# Final_Main.net
KiCad netlist of a schematic drawn in EasyEDA Pro
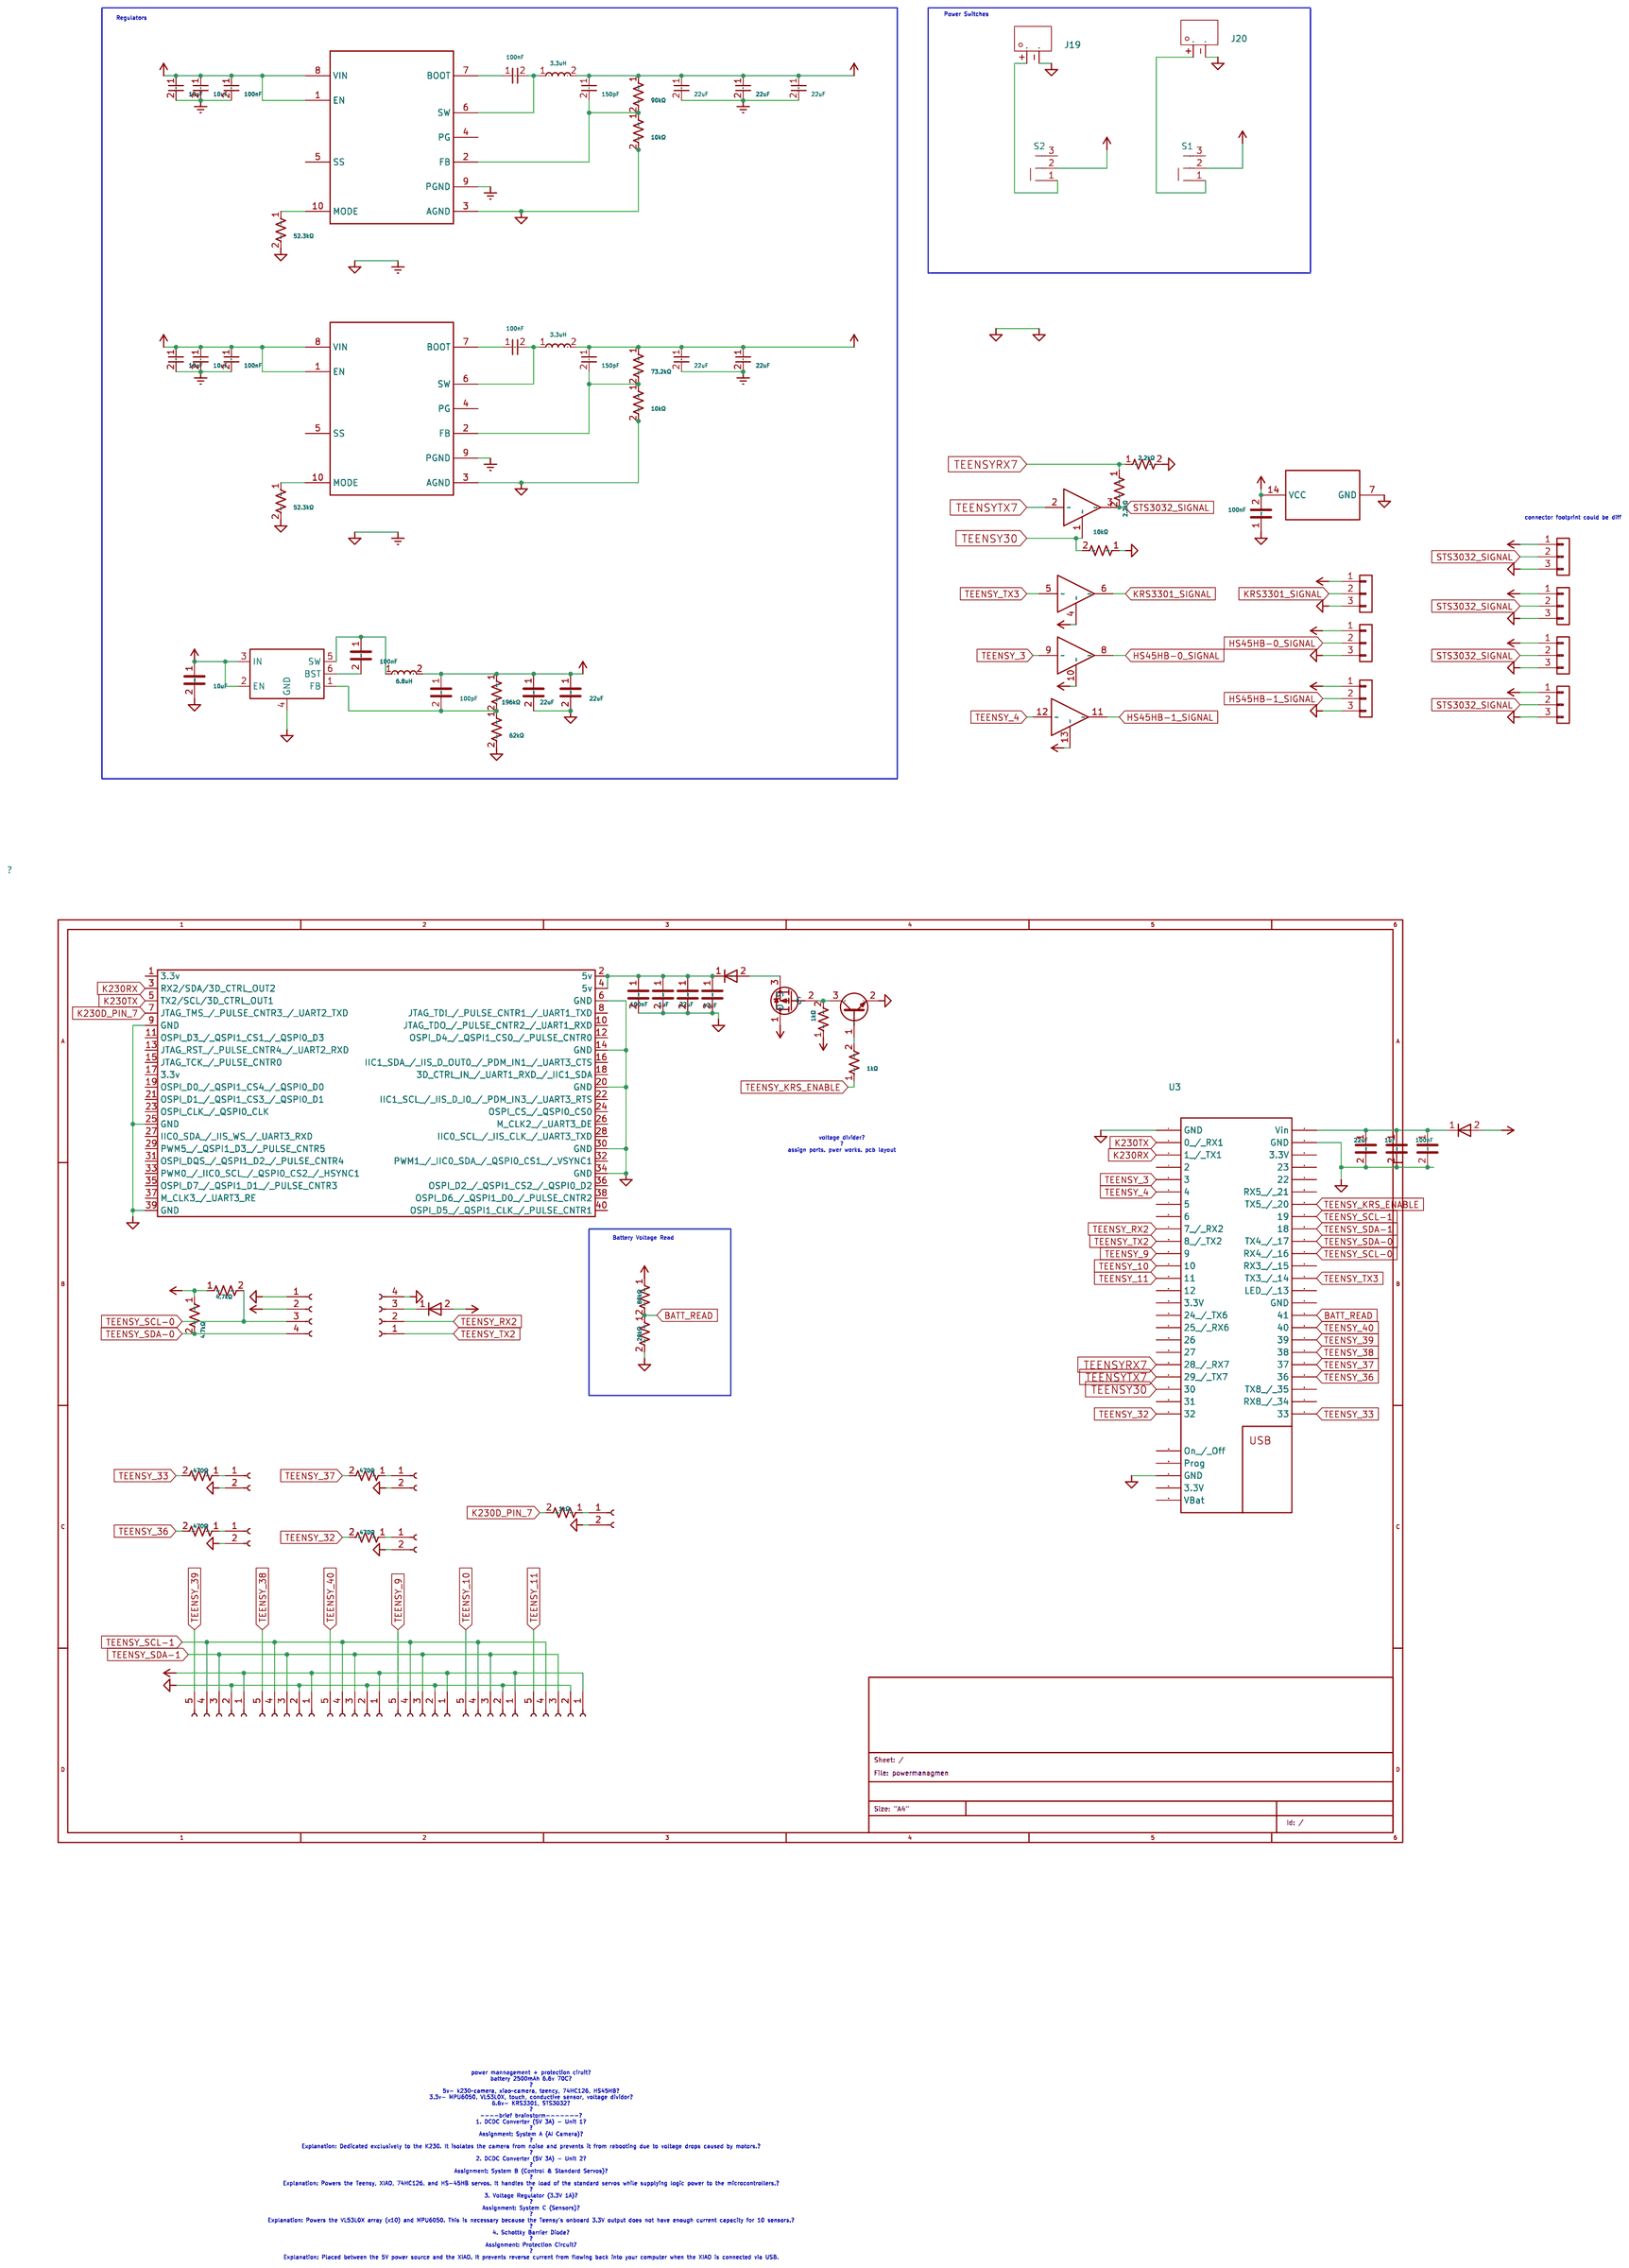
[diagram p0: schematic sheet]

(export (version "E")
  (design (tool "Eeschema 10.0.6"))
  (components
    (comp (ref "C1")
      (value "100nF")
      (description "Capacitance:100nF Tolerance:±10% Tolerance:±10% Voltage Rating:50V Temperature Coefficient:X7R")
      (fields
        (field (name "Manufacturer Part") "TCC0603X7R104K500CT")
        (field (name "Manufacturer") "CCTC(三环)")
      )
      (libsource (lib "easyedapro") (part "Device_C"))
    )
    (comp (ref "C2")
      (value "22uF")
      (description "Capacitance:22uF Tolerance:±20% Tolerance:±20% Voltage Rating:10V Temperature Coefficient:X5R")
      (fields
        (field (name "Manufacturer Part") "CL10A226MP8NUNE")
        (field (name "Manufacturer") "SAMSUNG(三星)")
      )
      (libsource (lib "easyedapro") (part "Device_C"))
    )
    (comp (ref "C3")
      (value "1uF")
      (description "Capacitance:1uF Tolerance:±10% Tolerance:±10% Voltage Rating:50V Temperature Coefficient:X5R")
      (fields
        (field (name "Manufacturer Part") "CL10A105KB8NNNC")
        (field (name "Manufacturer") "SAMSUNG(三星)")
      )
      (libsource (lib "easyedapro") (part "Device_C"))
    )
    (comp (ref "C4")
      (value "100nF")
      (description "Capacitance:100nF Tolerance:±10% Tolerance:±10% Voltage Rating:50V Temperature Coefficient:X7R")
      (fields
        (field (name "Manufacturer Part") "TCC0603X7R104K500CT")
        (field (name "Manufacturer") "CCTC(三环)")
      )
      (libsource (lib "easyedapro") (part "Device_C"))
    )
    (comp (ref "C5")
      (value "10uF")
      (description "Capacitance:10uF Tolerance:±20% Tolerance:±20% Voltage Rating:16V Temperature Coefficient:X5R")
      (fields
        (field (name "Manufacturer Part") "CL10A106MO8NQNC")
        (field (name "Manufacturer") "SAMSUNG(三星)")
      )
      (libsource (lib "easyedapro") (part "Device_C_Small"))
    )
    (comp (ref "C6")
      (value "22uF")
      (description "Capacitance:22uF Tolerance:±20% Tolerance:±20% Voltage Rating:10V Temperature Coefficient:X5R")
      (fields
        (field (name "Manufacturer Part") "CL10A226MP8NUNE")
        (field (name "Manufacturer") "SAMSUNG(三星)")
      )
      (libsource (lib "easyedapro") (part "Device_C_Small"))
    )
    (comp (ref "C7")
      (value "22uF")
      (description "Capacitance:22uF Tolerance:±20% Tolerance:±20% Voltage Rating:10V Temperature Coefficient:X5R")
      (fields
        (field (name "Manufacturer Part") "CL10A226MP8NUNE")
        (field (name "Manufacturer") "SAMSUNG(三星)")
      )
      (libsource (lib "easyedapro") (part "Device_C_Small"))
    )
    (comp (ref "C8")
      (value "22uF")
      (description "Capacitance:22uF Tolerance:±20% Tolerance:±20% Voltage Rating:10V Temperature Coefficient:X5R")
      (fields
        (field (name "Manufacturer Part") "CL10A226MP8NUNE")
        (field (name "Manufacturer") "SAMSUNG(三星)")
      )
      (libsource (lib "easyedapro") (part "Device_C_Small"))
    )
    (comp (ref "C10")
      (value "100pF")
      (description "Capacitance:100pF Tolerance:±5% Tolerance:±5% Voltage Rating:50V Temperature Coefficient:C0G")
      (fields
        (field (name "Manufacturer Part") "CL10C101JB8NNNC")
        (field (name "Manufacturer") "SAMSUNG(三星)")
      )
      (libsource (lib "easyedapro") (part "Device_C"))
    )
    (comp (ref "C12")
      (value "150pF")
      (description "Capacitance:150pF Tolerance:±10% Tolerance:±10% Voltage Rating:50V Temperature Coefficient:X7R")
      (fields (field (name "Manufacturer Part") "0603B151K500NT") (field (name "Manufacturer") "FH(风华)"))
      (libsource (lib "easyedapro") (part "Device_C_Small"))
    )
    (comp (ref "C17")
      (value "100nF")
      (description "Capacitance:100nF Tolerance:±10% Tolerance:±10% Voltage Rating:50V Temperature Coefficient:X7R")
      (fields
        (field (name "Manufacturer Part") "TCC0603X7R104K500CT")
        (field (name "Manufacturer") "CCTC(三环)")
      )
      (libsource (lib "easyedapro") (part "Device_C"))
    )
    (comp (ref "C18")
      (value "1uF")
      (description "Capacitance:1uF Tolerance:±10% Tolerance:±10% Voltage Rating:50V Temperature Coefficient:X5R")
      (fields
        (field (name "Manufacturer Part") "CL10A105KB8NNNC")
        (field (name "Manufacturer") "SAMSUNG(三星)")
      )
      (libsource (lib "easyedapro") (part "Device_C"))
    )
    (comp (ref "C19")
      (value "22uF")
      (description "Capacitance:22uF Tolerance:±20% Tolerance:±20% Voltage Rating:10V Temperature Coefficient:X5R")
      (fields
        (field (name "Manufacturer Part") "CL10A226MP8NUNE")
        (field (name "Manufacturer") "SAMSUNG(三星)")
      )
      (libsource (lib "easyedapro") (part "Device_C"))
    )
    (comp (ref "C20")
      (value "47uF")
      (description "Capacitance:47uF Tolerance:±20% Tolerance:±20% Voltage Rating:6.3V Temperature Coefficient:X5R")
      (fields
        (field (name "Manufacturer Part") "GRM188R60J476ME15D")
        (field (name "Manufacturer") "muRata(村田)")
      )
      (libsource (lib "easyedapro") (part "Device_C"))
    )
    (comp (ref "C21")
      (value "22uF")
      (description "Capacitance:22uF Tolerance:±20% Tolerance:±20% Voltage Rating:10V Temperature Coefficient:X5R")
      (fields
        (field (name "Manufacturer Part") "CL10A226MP8NUNE")
        (field (name "Manufacturer") "SAMSUNG(三星)")
      )
      (libsource (lib "easyedapro") (part "Device_C"))
    )
    (comp (ref "C22")
      (value "10uF")
      (description "Capacitance:10uF Tolerance:±20% Tolerance:±20% Voltage Rating:16V Temperature Coefficient:X5R")
      (fields
        (field (name "Manufacturer Part") "CL10A106MO8NQNC")
        (field (name "Manufacturer") "SAMSUNG(三星)")
      )
      (libsource (lib "easyedapro") (part "Device_C_Small"))
    )
    (comp (ref "C23")
      (value "100nF")
      (description "Capacitance:100nF Tolerance:±10% Tolerance:±10% Voltage Rating:50V Temperature Coefficient:X7R")
      (fields
        (field (name "Manufacturer Part") "TCC0603X7R104K500CT")
        (field (name "Manufacturer") "CCTC(三环)")
      )
      (libsource (lib "easyedapro") (part "Device_C"))
    )
    (comp (ref "C24")
      (value "100nF")
      (description "Capacitance:100nF Tolerance:±10% Tolerance:±10% Voltage Rating:50V Temperature Coefficient:X7R")
      (fields
        (field (name "Manufacturer Part") "TCC0603X7R104K500CT")
        (field (name "Manufacturer") "CCTC(三环)")
      )
      (libsource (lib "easyedapro") (part "Device_C_Small"))
    )
    (comp (ref "C28")
      (value "100nF")
      (description "Capacitance:100nF Tolerance:±10% Tolerance:±10% Voltage Rating:50V Temperature Coefficient:X7R")
      (fields
        (field (name "Manufacturer Part") "TCC0603X7R104K500CT")
        (field (name "Manufacturer") "CCTC(三环)")
      )
      (libsource (lib "easyedapro") (part "Device_C_Small"))
    )
    (comp (ref "C29")
      (value "22uF")
      (description "Capacitance:22uF Tolerance:±20% Tolerance:±20% Voltage Rating:10V Temperature Coefficient:X5R")
      (fields
        (field (name "Manufacturer Part") "CL10A226MP8NUNE")
        (field (name "Manufacturer") "SAMSUNG(三星)")
      )
      (libsource (lib "easyedapro") (part "Device_C"))
    )
    (comp (ref "C31")
      (value "10uF")
      (description "Capacitance:10uF Tolerance:±20% Tolerance:±20% Voltage Rating:16V Temperature Coefficient:X5R")
      (fields
        (field (name "Manufacturer Part") "CL10A106MO8NQNC")
        (field (name "Manufacturer") "SAMSUNG(三星)")
      )
      (libsource (lib "easyedapro") (part "Device_C"))
    )
    (comp (ref "C32")
      (value "100nF")
      (description "Capacitance:100nF Tolerance:±10% Tolerance:±10% Voltage Rating:50V Temperature Coefficient:X7R")
      (fields
        (field (name "Manufacturer Part") "TCC0603X7R104K500CT")
        (field (name "Manufacturer") "CCTC(三环)")
      )
      (libsource (lib "easyedapro") (part "Device_C_Small"))
    )
    (comp (ref "C33")
      (value "100nF")
      (description "Capacitance:100nF Tolerance:±10% Tolerance:±10% Voltage Rating:50V Temperature Coefficient:X7R")
      (fields
        (field (name "Manufacturer Part") "TCC0603X7R104K500CT")
        (field (name "Manufacturer") "CCTC(三环)")
      )
      (libsource (lib "easyedapro") (part "Device_C_Small"))
    )
    (comp (ref "C34")
      (value "10uF")
      (description "Capacitance:10uF Tolerance:±20% Tolerance:±20% Voltage Rating:16V Temperature Coefficient:X5R")
      (fields
        (field (name "Manufacturer Part") "CL10A106MO8NQNC")
        (field (name "Manufacturer") "SAMSUNG(三星)")
      )
      (libsource (lib "easyedapro") (part "Device_C_Small"))
    )
    (comp (ref "C35")
      (value "10uF")
      (description "Capacitance:10uF Tolerance:±20% Tolerance:±20% Voltage Rating:16V Temperature Coefficient:X5R")
      (fields
        (field (name "Manufacturer Part") "CL10A106MO8NQNC")
        (field (name "Manufacturer") "SAMSUNG(三星)")
      )
      (libsource (lib "easyedapro") (part "Device_C_Small"))
    )
    (comp (ref "C36")
      (value "22uF")
      (description "Capacitance:22uF Tolerance:±20% Tolerance:±20% Voltage Rating:10V Temperature Coefficient:X5R")
      (fields
        (field (name "Manufacturer Part") "CL10A226MP8NUNE")
        (field (name "Manufacturer") "SAMSUNG(三星)")
      )
      (libsource (lib "easyedapro") (part "Device_C_Small"))
    )
    (comp (ref "C37")
      (value "22uF")
      (description "Capacitance:22uF Tolerance:±20% Tolerance:±20% Voltage Rating:10V Temperature Coefficient:X5R")
      (fields
        (field (name "Manufacturer Part") "CL10A226MP8NUNE")
        (field (name "Manufacturer") "SAMSUNG(三星)")
      )
      (libsource (lib "easyedapro") (part "Device_C_Small"))
    )
    (comp (ref "C39")
      (value "150pF")
      (description "Capacitance:150pF Tolerance:±10% Tolerance:±10% Voltage Rating:50V Temperature Coefficient:X7R")
      (fields (field (name "Manufacturer Part") "0603B151K500NT") (field (name "Manufacturer") "FH(风华)"))
      (libsource (lib "easyedapro") (part "Device_C_Small"))
    )
    (comp (ref "D1")
      (value "BAT60B")
      (fields (field (name "Manufacturer") "R+O(宏嘉诚)"))
      (libsource (lib "easyedapro") (part "Diode_1N4148WT"))
    )
    (comp (ref "D2")
      (value "BAT60B")
      (fields (field (name "Manufacturer") "R+O(宏嘉诚)"))
      (libsource (lib "easyedapro") (part "Diode_1N4148WT"))
    )
    (comp (ref "D3")
      (value "BAT60B")
      (fields (field (name "Manufacturer") "R+O(宏嘉诚)"))
      (libsource (lib "easyedapro") (part "Diode_1N4148WT"))
    )
    (comp (ref "J1")
      (value "B3B-XH-A(LF)(SN)")
      (fields (field (name "Manufacturer") "JST"))
      (libsource (lib "easyedapro") (part "Connector_Generic_Conn_01x03"))
    )
    (comp (ref "J2")
      (value "PZ254V-11-03P")
      (fields (field (name "Manufacturer") "XFCN(兴飞)"))
      (libsource (lib "easyedapro") (part "Connector_Generic_Conn_01x03"))
    )
    (comp (ref "J3")
      (value "PZ254V-11-03P")
      (fields (field (name "Manufacturer") "XFCN(兴飞)"))
      (libsource (lib "easyedapro") (part "Connector_Generic_Conn_01x03"))
    )
    (comp (ref "J4")
      (value "PZ254V-11-03P")
      (fields (field (name "Manufacturer") "XFCN(兴飞)"))
      (libsource (lib "easyedapro") (part "Connector_Generic_Conn_01x03"))
    )
    (comp (ref "J5")
      (value "2.54-1*4P母")
      (fields (field (name "Manufacturer") "BOOMELE(博穆精密)"))
      (libsource (lib "easyedapro") (part "Connector_Conn_01x04_Socket"))
    )
    (comp (ref "J6")
      (value "PZ254V-11-02P")
      (fields (field (name "Manufacturer") "XFCN(兴飞)"))
      (libsource (lib "easyedapro") (part "Connector_Conn_01x02_Socket"))
    )
    (comp (ref "J7")
      (value "PZ254V-11-02P")
      (fields (field (name "Manufacturer") "XFCN(兴飞)"))
      (libsource (lib "easyedapro") (part "Connector_Conn_01x02_Socket"))
    )
    (comp (ref "J8")
      (value "PZ254V-11-02P")
      (fields (field (name "Manufacturer") "XFCN(兴飞)"))
      (libsource (lib "easyedapro") (part "Connector_Conn_01x02_Socket"))
    )
    (comp (ref "J9")
      (value "PZ254V-11-02P")
      (fields (field (name "Manufacturer") "XFCN(兴飞)"))
      (libsource (lib "easyedapro") (part "Connector_Conn_01x02_Socket"))
    )
    (comp (ref "J10")
      (value "PZ254V-11-02P")
      (fields (field (name "Manufacturer") "XFCN(兴飞)"))
      (libsource (lib "easyedapro") (part "Connector_Conn_01x02_Socket"))
    )
    (comp (ref "J12")
      (value "B3B-XH-A(LF)(SN)")
      (fields (field (name "Manufacturer") "JST"))
      (libsource (lib "easyedapro") (part "Connector_Generic_Conn_01x03"))
    )
    (comp (ref "J13")
      (value "B3B-XH-A(LF)(SN)")
      (fields (field (name "Manufacturer") "JST"))
      (libsource (lib "easyedapro") (part "Connector_Generic_Conn_01x03"))
    )
    (comp (ref "J14")
      (value "B3B-XH-A(LF)(SN)")
      (fields (field (name "Manufacturer") "JST"))
      (libsource (lib "easyedapro") (part "Connector_Generic_Conn_01x03"))
    )
    (comp (ref "J18")
      (value "B5B-PH-K-S(LF)(SN)")
      (fields (field (name "Manufacturer") "JST"))
      (libsource (lib "easyedapro") (part "Connector_Conn_01x05_Socket"))
    )
    (comp (ref "J19")
      (value "XT60-F")
      (footprint "easyedapro:CONN-TH_XT60PB-F")
      (fields (field (name "Manufacturer") "AMASS(艾迈斯)"))
      (libsource (lib "easyedapro") (part "XT60-F"))
    )
    (comp (ref "J20")
      (value "XT60-F")
      (footprint "easyedapro:CONN-TH_XT60PB-F")
      (fields (field (name "Manufacturer") "AMASS(艾迈斯)"))
      (libsource (lib "easyedapro") (part "XT60-F"))
    )
    (comp (ref "J25")
      (value "B5B-PH-K-S(LF)(SN)")
      (fields (field (name "Manufacturer") "JST"))
      (libsource (lib "easyedapro") (part "Connector_Conn_01x05_Socket"))
    )
    (comp (ref "J26")
      (value "B5B-PH-K-S(LF)(SN)")
      (fields (field (name "Manufacturer") "JST"))
      (libsource (lib "easyedapro") (part "Connector_Conn_01x05_Socket"))
    )
    (comp (ref "J27")
      (value "B5B-PH-K-S(LF)(SN)")
      (fields (field (name "Manufacturer") "JST"))
      (libsource (lib "easyedapro") (part "Connector_Conn_01x05_Socket"))
    )
    (comp (ref "J28")
      (value "B5B-PH-K-S(LF)(SN)")
      (fields (field (name "Manufacturer") "JST"))
      (libsource (lib "easyedapro") (part "Connector_Conn_01x05_Socket"))
    )
    (comp (ref "J29")
      (value "B5B-PH-K-S(LF)(SN)")
      (fields (field (name "Manufacturer") "JST"))
      (libsource (lib "easyedapro") (part "Connector_Conn_01x05_Socket"))
    )
    (comp (ref "J31")
      (value "22035045")
      (fields (field (name "Manufacturer") "MOLEX"))
      (libsource (lib "easyedapro") (part "Connector_Conn_01x04_Socket"))
    )
    (comp (ref "L1")
      (value "3.3uH")
      (description "Inductance: Tolerance:±20% Tolerance:±20% Current Rating: DC Resistance(DCR):19.9mΩ")
      (fields (field (name "Manufacturer Part") "CYA0650-3.3UH") (field (name "Manufacturer") "SHOU HAN(首韩)"))
      (libsource (lib "easyedapro") (part "Device_L"))
    )
    (comp (ref "L3")
      (value "6.8uH")
      (fields
        (field (name "Manufacturer Part") "MGFL2012F6R8MT-LF")
        (field (name "Manufacturer") "microgate(麦捷科技)")
      )
      (libsource (lib "easyedapro") (part "Device_L"))
    )
    (comp (ref "L4")
      (value "3.3uH")
      (description "Inductance: Tolerance:±20% Tolerance:±20% Current Rating: DC Resistance(DCR):19.9mΩ")
      (fields (field (name "Manufacturer Part") "CYA0650-3.3UH") (field (name "Manufacturer") "SHOU HAN(首韩)"))
      (libsource (lib "easyedapro") (part "Device_L"))
    )
    (comp (ref "Q1")
      (value "AO3401A")
      (fields (field (name "Manufacturer") "UMW(友台半导体)"))
      (libsource (lib "easyedapro") (part "Simulation_SPICE_PMOS"))
    )
    (comp (ref "Q2")
      (value "SS8050(RANGE:200-350)")
      (fields (field (name "Manufacturer") "CJ(江苏长电/长晶)"))
      (libsource (lib "easyedapro") (part "Transistor_BJT_SS8050"))
    )
    (comp (ref "R1")
      (value "10kΩ")
      (fields
        (field (name "Manufacturer Part") "0603WAF1002T5E")
        (field (name "Manufacturer") "UNI-ROYAL(厚声)")
      )
      (libsource (lib "easyedapro") (part "Device_R_US"))
    )
    (comp (ref "R2")
      (value "4.7kΩ")
      (fields (field (name "Manufacturer Part") "FRC0603F4701TS") (field (name "Manufacturer") "FOJAN(富捷)"))
      (libsource (lib "easyedapro") (part "Device_R_US"))
    )
    (comp (ref "R3")
      (value "4.7kΩ")
      (fields (field (name "Manufacturer Part") "FRC0603F4701TS") (field (name "Manufacturer") "FOJAN(富捷)"))
      (libsource (lib "easyedapro") (part "Device_R_US"))
    )
    (comp (ref "R4")
      (value "470Ω")
      (fields
        (field (name "Manufacturer Part") "0603WAF4700T5E")
        (field (name "Manufacturer") "UNI-ROYAL(厚声)")
      )
      (libsource (lib "easyedapro") (part "Device_R_US"))
    )
    (comp (ref "R5")
      (value "470Ω")
      (fields
        (field (name "Manufacturer Part") "0603WAF4700T5E")
        (field (name "Manufacturer") "UNI-ROYAL(厚声)")
      )
      (libsource (lib "easyedapro") (part "Device_R_US"))
    )
    (comp (ref "R6")
      (value "470Ω")
      (fields
        (field (name "Manufacturer Part") "0603WAF4700T5E")
        (field (name "Manufacturer") "UNI-ROYAL(厚声)")
      )
      (libsource (lib "easyedapro") (part "Device_R_US"))
    )
    (comp (ref "R7")
      (value "470Ω")
      (fields
        (field (name "Manufacturer Part") "0603WAF4700T5E")
        (field (name "Manufacturer") "UNI-ROYAL(厚声)")
      )
      (libsource (lib "easyedapro") (part "Device_R_US"))
    )
    (comp (ref "R8")
      (value "1kΩ")
      (fields
        (field (name "Manufacturer Part") "0603WAF1001T5E")
        (field (name "Manufacturer") "UNI-ROYAL(厚声)")
      )
      (libsource (lib "easyedapro") (part "Device_R_US"))
    )
    (comp (ref "R9")
      (value "2.2kΩ")
      (fields
        (field (name "Manufacturer Part") "0603WAF2201T5E")
        (field (name "Manufacturer") "UNI-ROYAL(厚声)")
      )
      (libsource (lib "easyedapro") (part "Device_R_US"))
    )
    (comp (ref "R10")
      (value "2.2kΩ")
      (fields
        (field (name "Manufacturer Part") "0603WAF2201T5E")
        (field (name "Manufacturer") "UNI-ROYAL(厚声)")
      )
      (libsource (lib "easyedapro") (part "Device_R_US"))
    )
    (comp (ref "R11")
      (value "52.3kΩ")
      (fields (field (name "Manufacturer Part") "FRC0603F5232TS") (field (name "Manufacturer") "FOJAN(富捷)"))
      (libsource (lib "easyedapro") (part "Device_R_US"))
    )
    (comp (ref "R12")
      (value "196kΩ")
      (fields (field (name "Manufacturer Part") "FRC0603F1963TS") (field (name "Manufacturer") "FOJAN(富捷)"))
      (libsource (lib "easyedapro") (part "Device_R_US"))
    )
    (comp (ref "R13")
      (value "1kΩ")
      (fields
        (field (name "Manufacturer Part") "0603WAF1001T5E")
        (field (name "Manufacturer") "UNI-ROYAL(厚声)")
      )
      (libsource (lib "easyedapro") (part "Device_R_US"))
    )
    (comp (ref "R14")
      (value "1kΩ")
      (fields
        (field (name "Manufacturer Part") "0603WAF1001T5E")
        (field (name "Manufacturer") "UNI-ROYAL(厚声)")
      )
      (libsource (lib "easyedapro") (part "Device_R_US"))
    )
    (comp (ref "R15")
      (value "62kΩ")
      (fields (field (name "Manufacturer Part") "FRC0603F6202TS") (field (name "Manufacturer") "FOJAN(富捷)"))
      (libsource (lib "easyedapro") (part "Device_R_US"))
    )
    (comp (ref "R20")
      (value "90kΩ")
      (fields (field (name "Manufacturer Part") "RT1206DRE0790KL") (field (name "Manufacturer") "YAGEO(国巨)"))
      (libsource (lib "easyedapro") (part "Device_R_US"))
    )
    (comp (ref "R21")
      (value "10kΩ")
      (fields
        (field (name "Manufacturer Part") "0603WAF1002T5E")
        (field (name "Manufacturer") "UNI-ROYAL(厚声)")
      )
      (libsource (lib "easyedapro") (part "Device_R_US"))
    )
    (comp (ref "R22")
      (value "80kΩ")
      (fields (field (name "Manufacturer Part") "ARG03FTC8002N") (field (name "Manufacturer") "Viking(光颉)"))
      (libsource (lib "easyedapro") (part "Device_R_US"))
    )
    (comp (ref "R23")
      (value "20kΩ")
      (fields (field (name "Manufacturer Part") "FRC0603F2002TS") (field (name "Manufacturer") "FOJAN(富捷)"))
      (libsource (lib "easyedapro") (part "Device_R_US"))
    )
    (comp (ref "R24")
      (value "52.3kΩ")
      (fields (field (name "Manufacturer Part") "FRC0603F5232TS") (field (name "Manufacturer") "FOJAN(富捷)"))
      (libsource (lib "easyedapro") (part "Device_R_US"))
    )
    (comp (ref "R25")
      (value "73.2kΩ")
      (fields (field (name "Manufacturer Part") "FRC0603F7322TS") (field (name "Manufacturer") "FOJAN(富捷)"))
      (libsource (lib "easyedapro") (part "Device_R_US"))
    )
    (comp (ref "R26")
      (value "10kΩ")
      (fields
        (field (name "Manufacturer Part") "0603WAF1002T5E")
        (field (name "Manufacturer") "UNI-ROYAL(厚声)")
      )
      (libsource (lib "easyedapro") (part "Device_R_US"))
    )
    (comp (ref "S1")
      (value "SS-12M11G4")
      (footprint "easyedapro:SW-TH_XKB_SS-12M11XX")
      (fields (field (name "Manufacturer") "XKB Connection(中国星坤)"))
      (libsource (lib "easyedapro") (part "SS-12M11G4"))
    )
    (comp (ref "S2")
      (value "SS-12M11G4")
      (footprint "easyedapro:SW-TH_XKB_SS-12M11XX")
      (fields (field (name "Manufacturer") "XKB Connection(中国星坤)"))
      (libsource (lib "easyedapro") (part "SS-12M11G4"))
    )
    (comp (ref "U1")
      (value "DM74LS126AM")
      (fields (field (name "Manufacturer") "onsemi(安森美)"))
      (libsource (lib "easyedapro") (part "74xx_74LS126"))
    )
    (comp (ref "U2")
      (value "FH-00148")
      (fields (field (name "Manufacturer") "Liansheng(连盛)"))
      (libsource (lib "easyedapro") (part "K230D_K230D-Zero"))
    )
    (comp (ref "U3") (value "TEENSY 4.1") (libsource (lib "easyedapro") (part "TEENSY 4.1")))
    (comp (ref "U4")
      (value "AP63201WU-7")
      (fields (field (name "Manufacturer") "DIODES(美台)"))
      (libsource (lib "easyedapro") (part "Regulator_Switching_AP63201WU"))
    )
    (comp (ref "U5")
      (value "TPS56A37RPAR")
      (fields (field (name "Manufacturer") "TI(德州仪器)"))
      (libsource (lib "easyedapro") (part "2026-01-05_00-17-44_TPS56A37RPAR"))
    )
    (comp (ref "U6")
      (value "TPS56A37RPAR")
      (fields (field (name "Manufacturer") "TI(德州仪器)"))
      (libsource (lib "easyedapro") (part "2026-01-05_00-17-44_TPS56A37RPAR"))
    )
  )
  (nets
    (net (code "1") (name "+3.3V") (class "Default")
      (node (ref "C10") (pin "1") (pinfunction "~_1") (pintype "unspecified"))
      (node (ref "C21") (pin "1") (pinfunction "~_1") (pintype "unspecified"))
      (node (ref "C29") (pin "1") (pinfunction "~_1") (pintype "unspecified"))
      (node (ref "J18") (pin "1") (pinfunction "Pin_1_1") (pintype "unspecified"))
      (node (ref "J25") (pin "1") (pinfunction "Pin_1_1") (pintype "unspecified"))
      (node (ref "J26") (pin "1") (pinfunction "Pin_1_1") (pintype "unspecified"))
      (node (ref "J27") (pin "1") (pinfunction "Pin_1_1") (pintype "unspecified"))
      (node (ref "J28") (pin "1") (pinfunction "Pin_1_1") (pintype "unspecified"))
      (node (ref "J29") (pin "1") (pinfunction "Pin_1_1") (pintype "unspecified"))
      (node (ref "L3") (pin "2") (pinfunction "2_2") (pintype "unspecified"))
      (node (ref "R12") (pin "1") (pinfunction "~_1") (pintype "unspecified"))
      (node (ref "R2") (pin "1") (pinfunction "~_1") (pintype "unspecified"))
      (node (ref "R3") (pin "1") (pinfunction "~_1") (pintype "unspecified"))
    )
    (net (code "2") (name "+5V") (class "Default")
      (node (ref "C1") (pin "2") (pinfunction "~_2") (pintype "unspecified"))
      (node (ref "C36") (pin "1") (pinfunction "~_1") (pintype "unspecified"))
      (node (ref "C37") (pin "1") (pinfunction "~_1") (pintype "unspecified"))
      (node (ref "C39") (pin "1") (pinfunction "~_1") (pintype "unspecified"))
      (node (ref "D1") (pin "2") (pinfunction "A_2") (pintype "unspecified"))
      (node (ref "D3") (pin "2") (pinfunction "A_2") (pintype "unspecified"))
      (node (ref "L4") (pin "2") (pinfunction "2_2") (pintype "unspecified"))
      (node (ref "Q1") (pin "1") (pinfunction "D_1") (pintype "unspecified"))
      (node (ref "R13") (pin "1") (pinfunction "~_1") (pintype "unspecified"))
      (node (ref "R25") (pin "1") (pinfunction "~_1") (pintype "unspecified"))
      (node (ref "U1") (pin "10") (pinfunction "~_10") (pintype "input"))
      (node (ref "U1") (pin "13") (pinfunction "~_13") (pintype "input"))
      (node (ref "U1") (pin "14") (pinfunction "VCC_14") (pintype "unspecified"))
      (node (ref "U1") (pin "4") (pinfunction "~_4") (pintype "input"))
    )
    (net (code "3") (name "+6V") (class "Default")
      (node (ref "C12") (pin "1") (pinfunction "~_1") (pintype "unspecified"))
      (node (ref "C6") (pin "1") (pinfunction "~_1") (pintype "unspecified"))
      (node (ref "C7") (pin "1") (pinfunction "~_1") (pintype "unspecified"))
      (node (ref "C8") (pin "1") (pinfunction "~_1") (pintype "unspecified"))
      (node (ref "J1") (pin "1") (pinfunction "Pin_1_1") (pintype "unspecified"))
      (node (ref "J12") (pin "1") (pinfunction "Pin_1_1") (pintype "unspecified"))
      (node (ref "J13") (pin "1") (pinfunction "Pin_1_1") (pintype "unspecified"))
      (node (ref "J14") (pin "1") (pinfunction "Pin_1_1") (pintype "unspecified"))
      (node (ref "J3") (pin "1") (pinfunction "Pin_1_1") (pintype "unspecified"))
      (node (ref "J4") (pin "1") (pinfunction "Pin_1_1") (pintype "unspecified"))
      (node (ref "L1") (pin "2") (pinfunction "2_2") (pintype "unspecified"))
      (node (ref "R20") (pin "1") (pinfunction "~_1") (pintype "unspecified"))
    )
    (net (code "4") (name "+BATT") (class "Default")
      (node (ref "C22") (pin "1") (pinfunction "~_1") (pintype "unspecified"))
      (node (ref "C24") (pin "1") (pinfunction "~_1") (pintype "unspecified"))
      (node (ref "C31") (pin "1") (pinfunction "~_1") (pintype "unspecified"))
      (node (ref "C33") (pin "1") (pinfunction "~_1") (pintype "unspecified"))
      (node (ref "C34") (pin "1") (pinfunction "~_1") (pintype "unspecified"))
      (node (ref "C35") (pin "1") (pinfunction "~_1") (pintype "unspecified"))
      (node (ref "C5") (pin "1") (pinfunction "~_1") (pintype "unspecified"))
      (node (ref "J2") (pin "1") (pinfunction "Pin_1_1") (pintype "unspecified"))
      (node (ref "R22") (pin "1") (pinfunction "~_1") (pintype "unspecified"))
      (node (ref "S1") (pin "2") (pinfunction "2_2") (pintype "unspecified"))
      (node (ref "S2") (pin "2") (pinfunction "2_2") (pintype "unspecified"))
      (node (ref "U4") (pin "2") (pinfunction "EN_2") (pintype "input"))
      (node (ref "U4") (pin "3") (pinfunction "IN_3") (pintype "unspecified"))
      (node (ref "U5") (pin "1") (pinfunction "EN_1") (pintype "input"))
      (node (ref "U5") (pin "8") (pinfunction "VIN_8") (pintype "unspecified"))
      (node (ref "U6") (pin "1") (pinfunction "EN_1") (pintype "input"))
      (node (ref "U6") (pin "8") (pinfunction "VIN_8") (pintype "unspecified"))
    )
    (net (code "5") (name "AGND") (class "Default")
      (node (ref "R24") (pin "2") (pinfunction "~_2") (pintype "unspecified"))
      (node (ref "R26") (pin "2") (pinfunction "~_2") (pintype "unspecified"))
      (node (ref "U6") (pin "3") (pinfunction "AGND_3") (pintype "unspecified"))
    )
    (net (code "6") (name "AGND1") (class "Default")
      (node (ref "R11") (pin "2") (pinfunction "~_2") (pintype "unspecified"))
      (node (ref "R21") (pin "2") (pinfunction "~_2") (pintype "unspecified"))
      (node (ref "U5") (pin "3") (pinfunction "AGND_3") (pintype "unspecified"))
    )
    (net (code "7") (name "BATT_READ") (class "Default")
      (node (ref "R22") (pin "2") (pinfunction "~_2") (pintype "unspecified"))
      (node (ref "R23") (pin "1") (pinfunction "~_1") (pintype "unspecified"))
      (node (ref "U3") (pin "40") (pinfunction "41_40") (pintype "unspecified"))
    )
    (net (code "8") (name "HS45HB-0_SIGNAL") (class "Default")
      (node (ref "J3") (pin "2") (pinfunction "Pin_2_2") (pintype "unspecified"))
      (node (ref "U1") (pin "8") (pinfunction "~_8") (pintype "unspecified"))
    )
    (net (code "9") (name "HS45HB-1_SIGNAL") (class "Default")
      (node (ref "J4") (pin "2") (pinfunction "Pin_2_2") (pintype "unspecified"))
      (node (ref "U1") (pin "11") (pinfunction "~_11") (pintype "unspecified"))
    )
    (net (code "10") (name "K230D_PIN_7") (class "Default")
      (node (ref "R8") (pin "2") (pinfunction "~_2") (pintype "unspecified"))
      (node (ref "U2") (pin "7") (pinfunction "JTAG_TMS_/_PULSE_CNTR3_/_UART2_TXD_7") (pintype "output"))
    )
    (net (code "11") (name "K230RX") (class "Default")
      (node (ref "U2") (pin "3") (pinfunction "RX2/SDA/3D_CTRL_OUT2_3") (pintype "input"))
      (node (ref "U3") (pin "3") (pinfunction "1_/_TX1_3") (pintype "unspecified"))
    )
    (net (code "12") (name "K230TX") (class "Default")
      (node (ref "U2") (pin "5") (pinfunction "TX2/SCL/3D_CTRL_OUT1_5") (pintype "bidirectional"))
      (node (ref "U3") (pin "2") (pinfunction "0_/_RX1_2") (pintype "unspecified"))
    )
    (net (code "13") (name "KRS3301_SIGNAL") (class "Default")
      (node (ref "J2") (pin "2") (pinfunction "Pin_2_2") (pintype "unspecified"))
      (node (ref "U1") (pin "6") (pinfunction "~_6") (pintype "unspecified"))
    )
    (net (code "14") (name "MGND") (class "Default")
      (node (ref "C22") (pin "2") (pinfunction "~_2") (pintype "unspecified"))
      (node (ref "C24") (pin "2") (pinfunction "~_2") (pintype "unspecified"))
      (node (ref "C5") (pin "2") (pinfunction "~_2") (pintype "unspecified"))
      (node (ref "C6") (pin "2") (pinfunction "~_2") (pintype "unspecified"))
      (node (ref "C7") (pin "2") (pinfunction "~_2") (pintype "unspecified"))
      (node (ref "C8") (pin "2") (pinfunction "~_2") (pintype "unspecified"))
      (node (ref "J19") (pin "-") (pinfunction "2_-") (pintype "input"))
      (node (ref "U5") (pin "9") (pinfunction "PGND_9") (pintype "unspecified"))
    )
    (net (code "15") (name "Net-(D1-K)") (class "Default")
      (node (ref "C2") (pin "1") (pinfunction "~_1") (pintype "unspecified"))
      (node (ref "C3") (pin "1") (pinfunction "~_1") (pintype "unspecified"))
      (node (ref "C4") (pin "1") (pinfunction "~_1") (pintype "unspecified"))
      (node (ref "D1") (pin "1") (pinfunction "K_1") (pintype "unspecified"))
      (node (ref "U3") (pin "25") (pinfunction "Vin_25") (pintype "unspecified"))
    )
    (net (code "16") (name "Net-(D2-A)") (class "Default")
      (node (ref "D2") (pin "2") (pinfunction "A_2") (pintype "unspecified"))
      (node (ref "Q1") (pin "3") (pinfunction "S_3") (pintype "unspecified"))
    )
    (net (code "17") (name "Net-(D2-K)") (class "Default")
      (node (ref "C17") (pin "1") (pinfunction "~_1") (pintype "unspecified"))
      (node (ref "C18") (pin "1") (pinfunction "~_1") (pintype "unspecified"))
      (node (ref "C19") (pin "1") (pinfunction "~_1") (pintype "unspecified"))
      (node (ref "C20") (pin "1") (pinfunction "~_1") (pintype "unspecified"))
      (node (ref "D2") (pin "1") (pinfunction "K_1") (pintype "unspecified"))
      (node (ref "U2") (pin "2") (pinfunction "5v_2") (pintype "unspecified"))
      (node (ref "U2") (pin "4") (pinfunction "5v_4") (pintype "bidirectional"))
    )
    (net (code "18") (name "Net-(D3-K)") (class "Default")
      (node (ref "D3") (pin "1") (pinfunction "K_1") (pintype "unspecified"))
      (node (ref "J31") (pin "3") (pinfunction "Pin_3_3") (pintype "unspecified"))
    )
    (net (code "19") (name "Net-(J6-Pin_1)") (class "Default")
      (node (ref "J6") (pin "1") (pinfunction "Pin_1_1") (pintype "unspecified"))
      (node (ref "R4") (pin "1") (pinfunction "~_1") (pintype "unspecified"))
    )
    (net (code "20") (name "Net-(J7-Pin_1)") (class "Default")
      (node (ref "J7") (pin "1") (pinfunction "Pin_1_1") (pintype "unspecified"))
      (node (ref "R5") (pin "1") (pinfunction "~_1") (pintype "unspecified"))
    )
    (net (code "21") (name "Net-(J8-Pin_1)") (class "Default")
      (node (ref "J8") (pin "1") (pinfunction "Pin_1_1") (pintype "unspecified"))
      (node (ref "R6") (pin "1") (pinfunction "~_1") (pintype "unspecified"))
    )
    (net (code "22") (name "Net-(J9-Pin_1)") (class "Default")
      (node (ref "J9") (pin "1") (pinfunction "Pin_1_1") (pintype "unspecified"))
      (node (ref "R7") (pin "1") (pinfunction "~_1") (pintype "unspecified"))
    )
    (net (code "23") (name "Net-(J10-Pin_1)") (class "Default")
      (node (ref "J10") (pin "1") (pinfunction "Pin_1_1") (pintype "unspecified"))
      (node (ref "R8") (pin "1") (pinfunction "~_1") (pintype "unspecified"))
    )
    (net (code "24") (name "Net-(J19-1)") (class "Default")
      (node (ref "J19") (pin "+") (pinfunction "1_+") (pintype "input"))
      (node (ref "S2") (pin "1") (pinfunction "1_1") (pintype "unspecified"))
    )
    (net (code "25") (name "Net-(J20-1)") (class "Default")
      (node (ref "J20") (pin "+") (pinfunction "1_+") (pintype "input"))
      (node (ref "S1") (pin "1") (pinfunction "1_1") (pintype "unspecified"))
    )
    (net (code "26") (name "Net-(Q1-G)") (class "Default")
      (node (ref "Q1") (pin "2") (pinfunction "G_2") (pintype "input"))
      (node (ref "Q2") (pin "3") (pinfunction "C_3") (pintype "unspecified"))
      (node (ref "R13") (pin "2") (pinfunction "~_2") (pintype "unspecified"))
    )
    (net (code "27") (name "Net-(Q2-B)") (class "Default")
      (node (ref "Q2") (pin "1") (pinfunction "B_1") (pintype "input"))
      (node (ref "R14") (pin "2") (pinfunction "~_2") (pintype "unspecified"))
    )
    (net (code "28") (name "Net-(U4-BST)") (class "Default")
      (node (ref "C23") (pin "2") (pinfunction "~_2") (pintype "unspecified"))
      (node (ref "U4") (pin "6") (pinfunction "BST_6") (pintype "unspecified"))
    )
    (net (code "29") (name "Net-(U4-FB)") (class "Default")
      (node (ref "C10") (pin "2") (pinfunction "~_2") (pintype "unspecified"))
      (node (ref "R12") (pin "2") (pinfunction "~_2") (pintype "unspecified"))
      (node (ref "R15") (pin "1") (pinfunction "~_1") (pintype "unspecified"))
      (node (ref "U4") (pin "1") (pinfunction "FB_1") (pintype "input"))
    )
    (net (code "30") (name "Net-(U4-SW)") (class "Default")
      (node (ref "C23") (pin "1") (pinfunction "~_1") (pintype "unspecified"))
      (node (ref "L3") (pin "1") (pinfunction "1_1") (pintype "unspecified"))
      (node (ref "U4") (pin "5") (pinfunction "SW_5") (pintype "output"))
    )
    (net (code "31") (name "Net-(U5-BOOT)") (class "Default")
      (node (ref "C28") (pin "1") (pinfunction "~_1") (pintype "unspecified"))
      (node (ref "U5") (pin "7") (pinfunction "BOOT_7") (pintype "unspecified"))
    )
    (net (code "32") (name "Net-(U5-FB)") (class "Default")
      (node (ref "C12") (pin "2") (pinfunction "~_2") (pintype "unspecified"))
      (node (ref "R20") (pin "2") (pinfunction "~_2") (pintype "unspecified"))
      (node (ref "R21") (pin "1") (pinfunction "~_1") (pintype "unspecified"))
      (node (ref "U5") (pin "2") (pinfunction "FB_2") (pintype "unspecified"))
    )
    (net (code "33") (name "Net-(U5-MODE)") (class "Default")
      (node (ref "R11") (pin "1") (pinfunction "~_1") (pintype "unspecified"))
      (node (ref "U5") (pin "10") (pinfunction "MODE_10") (pintype "unspecified"))
    )
    (net (code "34") (name "Net-(U5-SW)") (class "Default")
      (node (ref "C28") (pin "2") (pinfunction "~_2") (pintype "unspecified"))
      (node (ref "L1") (pin "1") (pinfunction "1_1") (pintype "unspecified"))
      (node (ref "U5") (pin "6") (pinfunction "SW_6") (pintype "unspecified"))
    )
    (net (code "35") (name "Net-(U6-BOOT)") (class "Default")
      (node (ref "C32") (pin "1") (pinfunction "~_1") (pintype "unspecified"))
      (node (ref "U6") (pin "7") (pinfunction "BOOT_7") (pintype "unspecified"))
    )
    (net (code "36") (name "Net-(U6-FB)") (class "Default")
      (node (ref "C39") (pin "2") (pinfunction "~_2") (pintype "unspecified"))
      (node (ref "R25") (pin "2") (pinfunction "~_2") (pintype "unspecified"))
      (node (ref "R26") (pin "1") (pinfunction "~_1") (pintype "unspecified"))
      (node (ref "U6") (pin "2") (pinfunction "FB_2") (pintype "unspecified"))
    )
    (net (code "37") (name "Net-(U6-MODE)") (class "Default")
      (node (ref "R24") (pin "1") (pinfunction "~_1") (pintype "unspecified"))
      (node (ref "U6") (pin "10") (pinfunction "MODE_10") (pintype "unspecified"))
    )
    (net (code "38") (name "Net-(U6-SW)") (class "Default")
      (node (ref "C32") (pin "2") (pinfunction "~_2") (pintype "unspecified"))
      (node (ref "L4") (pin "1") (pinfunction "1_1") (pintype "unspecified"))
      (node (ref "U6") (pin "6") (pinfunction "SW_6") (pintype "unspecified"))
    )
    (net (code "39") (name "POWER_+3.3V") (class "Default")
      (node (ref "J5") (pin "2") (pinfunction "Pin_2_2") (pintype "unspecified"))
    )
    (net (code "40") (name "POWER_GND") (class "Default")
      (node (ref "C1") (pin "1") (pinfunction "~_1") (pintype "unspecified"))
      (node (ref "C17") (pin "2") (pinfunction "~_2") (pintype "unspecified"))
      (node (ref "C18") (pin "2") (pinfunction "~_2") (pintype "unspecified"))
      (node (ref "C19") (pin "2") (pinfunction "~_2") (pintype "unspecified"))
      (node (ref "C2") (pin "2") (pinfunction "~_2") (pintype "unspecified"))
      (node (ref "C20") (pin "2") (pinfunction "~_2") (pintype "unspecified"))
      (node (ref "C21") (pin "2") (pinfunction "~_2") (pintype "unspecified"))
      (node (ref "C29") (pin "2") (pinfunction "~_2") (pintype "unspecified"))
      (node (ref "C3") (pin "2") (pinfunction "~_2") (pintype "unspecified"))
      (node (ref "C31") (pin "2") (pinfunction "~_2") (pintype "unspecified"))
      (node (ref "C33") (pin "2") (pinfunction "~_2") (pintype "unspecified"))
      (node (ref "C34") (pin "2") (pinfunction "~_2") (pintype "unspecified"))
      (node (ref "C35") (pin "2") (pinfunction "~_2") (pintype "unspecified"))
      (node (ref "C36") (pin "2") (pinfunction "~_2") (pintype "unspecified"))
      (node (ref "C37") (pin "2") (pinfunction "~_2") (pintype "unspecified"))
      (node (ref "C4") (pin "2") (pinfunction "~_2") (pintype "unspecified"))
      (node (ref "J1") (pin "3") (pinfunction "Pin_3_3") (pintype "unspecified"))
      (node (ref "J10") (pin "2") (pinfunction "Pin_2_2") (pintype "unspecified"))
      (node (ref "J12") (pin "3") (pinfunction "Pin_3_3") (pintype "unspecified"))
      (node (ref "J13") (pin "3") (pinfunction "Pin_3_3") (pintype "unspecified"))
      (node (ref "J14") (pin "3") (pinfunction "Pin_3_3") (pintype "unspecified"))
      (node (ref "J18") (pin "2") (pinfunction "Pin_2_2") (pintype "unspecified"))
      (node (ref "J2") (pin "3") (pinfunction "Pin_3_3") (pintype "unspecified"))
      (node (ref "J20") (pin "-") (pinfunction "2_-") (pintype "input"))
      (node (ref "J25") (pin "2") (pinfunction "Pin_2_2") (pintype "unspecified"))
      (node (ref "J26") (pin "2") (pinfunction "Pin_2_2") (pintype "unspecified"))
      (node (ref "J27") (pin "2") (pinfunction "Pin_2_2") (pintype "unspecified"))
      (node (ref "J28") (pin "2") (pinfunction "Pin_2_2") (pintype "unspecified"))
      (node (ref "J29") (pin "2") (pinfunction "Pin_2_2") (pintype "unspecified"))
      (node (ref "J3") (pin "3") (pinfunction "Pin_3_3") (pintype "unspecified"))
      (node (ref "J31") (pin "4") (pinfunction "Pin_4_4") (pintype "unspecified"))
      (node (ref "J4") (pin "3") (pinfunction "Pin_3_3") (pintype "unspecified"))
      (node (ref "J5") (pin "1") (pinfunction "Pin_1_1") (pintype "unspecified"))
      (node (ref "J6") (pin "2") (pinfunction "Pin_2_2") (pintype "unspecified"))
      (node (ref "J7") (pin "2") (pinfunction "Pin_2_2") (pintype "unspecified"))
      (node (ref "J8") (pin "2") (pinfunction "Pin_2_2") (pintype "unspecified"))
      (node (ref "J9") (pin "2") (pinfunction "Pin_2_2") (pintype "unspecified"))
      (node (ref "Q2") (pin "2") (pinfunction "E_2") (pintype "unspecified"))
      (node (ref "R1") (pin "1") (pinfunction "~_1") (pintype "unspecified"))
      (node (ref "R10") (pin "2") (pinfunction "~_2") (pintype "unspecified"))
      (node (ref "R15") (pin "2") (pinfunction "~_2") (pintype "unspecified"))
      (node (ref "R23") (pin "2") (pinfunction "~_2") (pintype "unspecified"))
      (node (ref "U1") (pin "7") (pinfunction "GND_7") (pintype "unspecified"))
      (node (ref "U2") (pin "14") (pinfunction "GND_14") (pintype "bidirectional"))
      (node (ref "U2") (pin "20") (pinfunction "GND_20") (pintype "bidirectional"))
      (node (ref "U2") (pin "25") (pinfunction "GND_25") (pintype "bidirectional"))
      (node (ref "U2") (pin "30") (pinfunction "GND_30") (pintype "bidirectional"))
      (node (ref "U2") (pin "34") (pinfunction "GND_34") (pintype "bidirectional"))
      (node (ref "U2") (pin "39") (pinfunction "GND_39") (pintype "bidirectional"))
      (node (ref "U2") (pin "6") (pinfunction "GND_6") (pintype "bidirectional"))
      (node (ref "U2") (pin "9") (pinfunction "GND_9") (pintype "bidirectional"))
      (node (ref "U3") (pin "1") (pinfunction "GND_1") (pintype "unspecified"))
      (node (ref "U3") (pin "26") (pinfunction "GND_26") (pintype "unspecified"))
      (node (ref "U3") (pin "51") (pinfunction "GND_51") (pintype "unspecified"))
      (node (ref "U4") (pin "4") (pinfunction "GND_4") (pintype "unspecified"))
      (node (ref "U6") (pin "9") (pinfunction "PGND_9") (pintype "unspecified"))
    )
    (net (code "41") (name "STS3032_SIGNAL") (class "Default")
      (node (ref "J1") (pin "2") (pinfunction "Pin_2_2") (pintype "unspecified"))
      (node (ref "J12") (pin "2") (pinfunction "Pin_2_2") (pintype "unspecified"))
      (node (ref "J13") (pin "2") (pinfunction "Pin_2_2") (pintype "unspecified"))
      (node (ref "J14") (pin "2") (pinfunction "Pin_2_2") (pintype "unspecified"))
      (node (ref "R9") (pin "2") (pinfunction "~_2") (pintype "unspecified"))
      (node (ref "U1") (pin "3") (pinfunction "~_3") (pintype "unspecified"))
    )
    (net (code "42") (name "TEENSY30") (class "Default")
      (node (ref "R1") (pin "2") (pinfunction "~_2") (pintype "unspecified"))
      (node (ref "U1") (pin "1") (pinfunction "~_1") (pintype "input"))
      (node (ref "U3") (pin "22") (pinfunction "30_22") (pintype "unspecified"))
    )
    (net (code "43") (name "TEENSYRX7") (class "Default")
      (node (ref "R10") (pin "1") (pinfunction "~_1") (pintype "unspecified"))
      (node (ref "R9") (pin "1") (pinfunction "~_1") (pintype "unspecified"))
      (node (ref "U3") (pin "20") (pinfunction "28_/_RX7_20") (pintype "unspecified"))
    )
    (net (code "44") (name "TEENSYTX7") (class "Default")
      (node (ref "U1") (pin "2") (pinfunction "~_2") (pintype "input"))
      (node (ref "U3") (pin "21") (pinfunction "29_/_TX7_21") (pintype "unspecified"))
    )
    (net (code "45") (name "TEENSY_3") (class "Default")
      (node (ref "U1") (pin "9") (pinfunction "~_9") (pintype "input"))
      (node (ref "U3") (pin "5") (pinfunction "3_5") (pintype "unspecified"))
    )
    (net (code "46") (name "TEENSY_4") (class "Default")
      (node (ref "U1") (pin "12") (pinfunction "~_12") (pintype "input"))
      (node (ref "U3") (pin "6") (pinfunction "4_6") (pintype "unspecified"))
    )
    (net (code "47") (name "TEENSY_9") (class "Default")
      (node (ref "J27") (pin "5") (pinfunction "Pin_5_5") (pintype "unspecified"))
      (node (ref "U3") (pin "11") (pinfunction "9_11") (pintype "unspecified"))
    )
    (net (code "48") (name "TEENSY_10") (class "Default")
      (node (ref "J28") (pin "5") (pinfunction "Pin_5_5") (pintype "unspecified"))
      (node (ref "U3") (pin "12") (pinfunction "10_12") (pintype "unspecified"))
    )
    (net (code "49") (name "TEENSY_11") (class "Default")
      (node (ref "J29") (pin "5") (pinfunction "Pin_5_5") (pintype "unspecified"))
      (node (ref "U3") (pin "13") (pinfunction "11_13") (pintype "unspecified"))
    )
    (net (code "50") (name "TEENSY_32") (class "Default")
      (node (ref "R7") (pin "2") (pinfunction "~_2") (pintype "unspecified"))
      (node (ref "U3") (pin "24") (pinfunction "32_24") (pintype "unspecified"))
    )
    (net (code "51") (name "TEENSY_33") (class "Default")
      (node (ref "R4") (pin "2") (pinfunction "~_2") (pintype "unspecified"))
      (node (ref "U3") (pin "48") (pinfunction "33_48") (pintype "unspecified"))
    )
    (net (code "52") (name "TEENSY_36") (class "Default")
      (node (ref "R5") (pin "2") (pinfunction "~_2") (pintype "unspecified"))
      (node (ref "U3") (pin "45") (pinfunction "36_45") (pintype "unspecified"))
    )
    (net (code "53") (name "TEENSY_37") (class "Default")
      (node (ref "R6") (pin "2") (pinfunction "~_2") (pintype "unspecified"))
      (node (ref "U3") (pin "44") (pinfunction "37_44") (pintype "unspecified"))
    )
    (net (code "54") (name "TEENSY_38") (class "Default")
      (node (ref "J18") (pin "5") (pinfunction "Pin_5_5") (pintype "unspecified"))
      (node (ref "U3") (pin "43") (pinfunction "38_43") (pintype "unspecified"))
    )
    (net (code "55") (name "TEENSY_39") (class "Default")
      (node (ref "J25") (pin "5") (pinfunction "Pin_5_5") (pintype "unspecified"))
      (node (ref "U3") (pin "42") (pinfunction "39_42") (pintype "unspecified"))
    )
    (net (code "56") (name "TEENSY_40") (class "Default")
      (node (ref "J26") (pin "5") (pinfunction "Pin_5_5") (pintype "unspecified"))
      (node (ref "U3") (pin "41") (pinfunction "40_41") (pintype "unspecified"))
    )
    (net (code "57") (name "TEENSY_KRS_ENABLE") (class "Default")
      (node (ref "R14") (pin "1") (pinfunction "~_1") (pintype "unspecified"))
      (node (ref "U3") (pin "31") (pinfunction "TX5_/_20_31") (pintype "unspecified"))
    )
    (net (code "58") (name "TEENSY_RX2") (class "Default")
      (node (ref "J31") (pin "2") (pinfunction "Pin_2_2") (pintype "unspecified"))
      (node (ref "U3") (pin "9") (pinfunction "7_/_RX2_9") (pintype "unspecified"))
    )
    (net (code "59") (name "TEENSY_SCL-0") (class "Default")
      (node (ref "J5") (pin "3") (pinfunction "Pin_3_3") (pintype "unspecified"))
      (node (ref "R3") (pin "2") (pinfunction "~_2") (pintype "unspecified"))
      (node (ref "U3") (pin "35") (pinfunction "RX4_/_16_35") (pintype "unspecified"))
    )
    (net (code "60") (name "TEENSY_SCL-1") (class "Default")
      (node (ref "J18") (pin "4") (pinfunction "Pin_4_4") (pintype "unspecified"))
      (node (ref "J25") (pin "4") (pinfunction "Pin_4_4") (pintype "unspecified"))
      (node (ref "J26") (pin "4") (pinfunction "Pin_4_4") (pintype "unspecified"))
      (node (ref "J27") (pin "4") (pinfunction "Pin_4_4") (pintype "unspecified"))
      (node (ref "J28") (pin "4") (pinfunction "Pin_4_4") (pintype "unspecified"))
      (node (ref "J29") (pin "4") (pinfunction "Pin_4_4") (pintype "unspecified"))
      (node (ref "U3") (pin "32") (pinfunction "19_32") (pintype "unspecified"))
    )
    (net (code "61") (name "TEENSY_SDA-0") (class "Default")
      (node (ref "J5") (pin "4") (pinfunction "Pin_4_4") (pintype "unspecified"))
      (node (ref "R2") (pin "2") (pinfunction "~_2") (pintype "unspecified"))
      (node (ref "U3") (pin "34") (pinfunction "TX4_/_17_34") (pintype "unspecified"))
    )
    (net (code "62") (name "TEENSY_SDA-1") (class "Default")
      (node (ref "J18") (pin "3") (pinfunction "Pin_3_3") (pintype "unspecified"))
      (node (ref "J25") (pin "3") (pinfunction "Pin_3_3") (pintype "unspecified"))
      (node (ref "J26") (pin "3") (pinfunction "Pin_3_3") (pintype "unspecified"))
      (node (ref "J27") (pin "3") (pinfunction "Pin_3_3") (pintype "unspecified"))
      (node (ref "J28") (pin "3") (pinfunction "Pin_3_3") (pintype "unspecified"))
      (node (ref "J29") (pin "3") (pinfunction "Pin_3_3") (pintype "unspecified"))
      (node (ref "U3") (pin "33") (pinfunction "18_33") (pintype "unspecified"))
    )
    (net (code "63") (name "TEENSY_TX2") (class "Default")
      (node (ref "J31") (pin "1") (pinfunction "Pin_1_1") (pintype "unspecified"))
      (node (ref "U3") (pin "10") (pinfunction "8_/_TX2_10") (pintype "unspecified"))
    )
    (net (code "64") (name "TEENSY_TX3") (class "Default")
      (node (ref "U1") (pin "5") (pinfunction "~_5") (pintype "input"))
      (node (ref "U3") (pin "37") (pinfunction "TX3_/_14_37") (pintype "unspecified"))
    )
    (net (code "65") (name "unconnected-(S1-Pad3)") (class "Default")
      (node (ref "S1") (pin "3") (pinfunction "3_3") (pintype "unspecified"))
    )
    (net (code "66") (name "unconnected-(S2-Pad3)") (class "Default")
      (node (ref "S2") (pin "3") (pinfunction "3_3") (pintype "unspecified"))
    )
    (net (code "67") (name "unconnected-(U2-3.3v-Pad1)") (class "Default")
      (node (ref "U2") (pin "1") (pinfunction "3.3v_1") (pintype "unspecified"))
    )
    (net (code "68") (name "unconnected-(U2-3.3v-Pad17)") (class "Default")
      (node (ref "U2") (pin "17") (pinfunction "3.3v_17") (pintype "bidirectional"))
    )
    (net (code "69") (name "unconnected-(U2-3D_CTRL_IN_{slash}_UART1_RXD_{slash}_IIC1_SDA-Pad18)") (class "Default")
      (node (ref "U2") (pin "18") (pinfunction "3D_CTRL_IN_/_UART1_RXD_/_IIC1_SDA_18") (pintype "bidirectional"))
    )
    (net (code "70") (name "unconnected-(U2-IIC0_SCL_{slash}_IIS_CLK_{slash}_UART3_TXD-Pad28)") (class "Default")
      (node (ref "U2") (pin "28") (pinfunction "IIC0_SCL_/_IIS_CLK_/_UART3_TXD_28") (pintype "bidirectional"))
    )
    (net (code "71") (name "unconnected-(U2-IIC0_SDA_{slash}_IIS_WS_{slash}_UART3_RXD-Pad27)") (class "Default")
      (node (ref "U2") (pin "27") (pinfunction "IIC0_SDA_/_IIS_WS_/_UART3_RXD_27") (pintype "bidirectional"))
    )
    (net (code "72") (name "unconnected-(U2-IIC1_SCL_{slash}_IIS_D_I0_{slash}_PDM_IN3_{slash}_UART3_RTS-Pad22)") (class "Default")
      (node (ref "U2") (pin "22") (pinfunction "IIC1_SCL_/_IIS_D_I0_/_PDM_IN3_/_UART3_RTS_22") (pintype "bidirectional"))
    )
    (net (code "73") (name "unconnected-(U2-IIC1_SDA_{slash}_IIS_D_OUT0_{slash}_PDM_IN1_{slash}_UART3_CTS-Pad16)") (class "Default")
      (node (ref "U2") (pin "16") (pinfunction "IIC1_SDA_/_IIS_D_OUT0_/_PDM_IN1_/_UART3_CTS_16") (pintype "bidirectional"))
    )
    (net (code "74") (name "unconnected-(U2-JTAG_RST_{slash}_PULSE_CNTR4_{slash}_UART2_RXD-Pad13)") (class "Default")
      (node (ref "U2") (pin "13") (pinfunction "JTAG_RST_/_PULSE_CNTR4_/_UART2_RXD_13") (pintype "bidirectional"))
    )
    (net (code "75") (name "unconnected-(U2-JTAG_TCK_{slash}_PULSE_CNTR0-Pad15)") (class "Default")
      (node (ref "U2") (pin "15") (pinfunction "JTAG_TCK_/_PULSE_CNTR0_15") (pintype "bidirectional"))
    )
    (net (code "76") (name "unconnected-(U2-JTAG_TDI_{slash}_PULSE_CNTR1_{slash}_UART1_TXD-Pad8)") (class "Default")
      (node (ref "U2") (pin "8") (pinfunction "JTAG_TDI_/_PULSE_CNTR1_/_UART1_TXD_8") (pintype "bidirectional"))
    )
    (net (code "77") (name "unconnected-(U2-JTAG_TDO_{slash}_PULSE_CNTR2_{slash}_UART1_RXD-Pad10)") (class "Default")
      (node (ref "U2") (pin "10") (pinfunction "JTAG_TDO_/_PULSE_CNTR2_/_UART1_RXD_10") (pintype "bidirectional"))
    )
    (net (code "78") (name "unconnected-(U2-M_CLK2_{slash}_UART3_DE-Pad26)") (class "Default")
      (node (ref "U2") (pin "26") (pinfunction "M_CLK2_/_UART3_DE_26") (pintype "bidirectional"))
    )
    (net (code "79") (name "unconnected-(U2-M_CLK3_{slash}_UART3_RE-Pad37)") (class "Default")
      (node (ref "U2") (pin "37") (pinfunction "M_CLK3_/_UART3_RE_37") (pintype "bidirectional"))
    )
    (net (code "80") (name "unconnected-(U2-OSPI_CLK_{slash}_QSPI0_CLK-Pad23)") (class "Default")
      (node (ref "U2") (pin "23") (pinfunction "OSPI_CLK_/_QSPI0_CLK_23") (pintype "bidirectional"))
    )
    (net (code "81") (name "unconnected-(U2-OSPI_CS_{slash}_QSPI0_CS0-Pad24)") (class "Default")
      (node (ref "U2") (pin "24") (pinfunction "OSPI_CS_/_QSPI0_CS0_24") (pintype "bidirectional"))
    )
    (net (code "82") (name "unconnected-(U2-OSPI_D0_{slash}_QSPI1_CS4_{slash}_QSPI0_D0-Pad19)") (class "Default")
      (node (ref "U2") (pin "19") (pinfunction "OSPI_D0_/_QSPI1_CS4_/_QSPI0_D0_19") (pintype "bidirectional"))
    )
    (net (code "83") (name "unconnected-(U2-OSPI_D1_{slash}_QSPI1_CS3_{slash}_QSPI0_D1-Pad21)") (class "Default")
      (node (ref "U2") (pin "21") (pinfunction "OSPI_D1_/_QSPI1_CS3_/_QSPI0_D1_21") (pintype "bidirectional"))
    )
    (net (code "84") (name "unconnected-(U2-OSPI_D2_{slash}_QSPI1_CS2_{slash}_QSPI0_D2-Pad36)") (class "Default")
      (node (ref "U2") (pin "36") (pinfunction "OSPI_D2_/_QSPI1_CS2_/_QSPI0_D2_36") (pintype "bidirectional"))
    )
    (net (code "85") (name "unconnected-(U2-OSPI_D3_{slash}_QSPI1_CS1_{slash}_QSPI0_D3-Pad11)") (class "Default")
      (node (ref "U2") (pin "11") (pinfunction "OSPI_D3_/_QSPI1_CS1_/_QSPI0_D3_11") (pintype "bidirectional"))
    )
    (net (code "86") (name "unconnected-(U2-OSPI_D4_{slash}_QSPI1_CS0_{slash}_PULSE_CNTR0-Pad12)") (class "Default")
      (node (ref "U2") (pin "12") (pinfunction "OSPI_D4_/_QSPI1_CS0_/_PULSE_CNTR0_12") (pintype "bidirectional"))
    )
    (net (code "87") (name "unconnected-(U2-OSPI_D5_{slash}_QSPI1_CLK_{slash}_PULSE_CNTR1-Pad40)") (class "Default")
      (node (ref "U2") (pin "40") (pinfunction "OSPI_D5_/_QSPI1_CLK_/_PULSE_CNTR1_40") (pintype "bidirectional"))
    )
    (net (code "88") (name "unconnected-(U2-OSPI_D6_{slash}_QSPI1_D0_{slash}_PULSE_CNTR2-Pad38)") (class "Default")
      (node (ref "U2") (pin "38") (pinfunction "OSPI_D6_/_QSPI1_D0_/_PULSE_CNTR2_38") (pintype "bidirectional"))
    )
    (net (code "89") (name "unconnected-(U2-OSPI_D7_{slash}_QSPI1_D1_{slash}_PULSE_CNTR3-Pad35)") (class "Default")
      (node (ref "U2") (pin "35") (pinfunction "OSPI_D7_/_QSPI1_D1_/_PULSE_CNTR3_35") (pintype "bidirectional"))
    )
    (net (code "90") (name "unconnected-(U2-OSPI_DQS_{slash}_QSPI1_D2_{slash}_PULSE_CNTR4-Pad31)") (class "Default")
      (node (ref "U2") (pin "31") (pinfunction "OSPI_DQS_/_QSPI1_D2_/_PULSE_CNTR4_31") (pintype "bidirectional"))
    )
    (net (code "91") (name "unconnected-(U2-PWM0_{slash}_IIC0_SCL_{slash}_QSPI0_CS2_{slash}_HSYNC1-Pad33)") (class "Default")
      (node (ref "U2") (pin "33") (pinfunction "PWM0_/_IIC0_SCL_/_QSPI0_CS2_/_HSYNC1_33") (pintype "bidirectional"))
    )
    (net (code "92") (name "unconnected-(U2-PWM1_{slash}_IIC0_SDA_{slash}_QSPI0_CS1_{slash}_VSYNC1-Pad32)") (class "Default")
      (node (ref "U2") (pin "32") (pinfunction "PWM1_/_IIC0_SDA_/_QSPI0_CS1_/_VSYNC1_32") (pintype "bidirectional"))
    )
    (net (code "93") (name "unconnected-(U2-PWM5_{slash}_QSPI1_D3_{slash}_PULSE_CNTR5-Pad29)") (class "Default")
      (node (ref "U2") (pin "29") (pinfunction "PWM5_/_QSPI1_D3_/_PULSE_CNTR5_29") (pintype "bidirectional"))
    )
    (net (code "94") (name "unconnected-(U3-2-Pad4)") (class "Default")
      (node (ref "U3") (pin "4") (pinfunction "2_4") (pintype "unspecified"))
    )
    (net (code "95") (name "unconnected-(U3-3.3V-Pad15)") (class "Default")
      (node (ref "U3") (pin "15") (pinfunction "3.3V_15") (pintype "unspecified"))
    )
    (net (code "96") (name "unconnected-(U3-3.3V-Pad27)") (class "Default")
      (node (ref "U3") (pin "27") (pinfunction "3.3V_27") (pintype "unspecified"))
    )
    (net (code "97") (name "unconnected-(U3-3.3V-Pad52)") (class "Default")
      (node (ref "U3") (pin "52") (pinfunction "3.3V_52") (pintype "unspecified"))
    )
    (net (code "98") (name "unconnected-(U3-5-Pad7)") (class "Default")
      (node (ref "U3") (pin "7") (pinfunction "5_7") (pintype "unspecified"))
    )
    (net (code "99") (name "unconnected-(U3-6-Pad8)") (class "Default")
      (node (ref "U3") (pin "8") (pinfunction "6_8") (pintype "unspecified"))
    )
    (net (code "100") (name "unconnected-(U3-12-Pad14)") (class "Default")
      (node (ref "U3") (pin "14") (pinfunction "12_14") (pintype "unspecified"))
    )
    (net (code "101") (name "unconnected-(U3-22-Pad29)") (class "Default")
      (node (ref "U3") (pin "29") (pinfunction "22_29") (pintype "unspecified"))
    )
    (net (code "102") (name "unconnected-(U3-23-Pad28)") (class "Default")
      (node (ref "U3") (pin "28") (pinfunction "23_28") (pintype "unspecified"))
    )
    (net (code "103") (name "unconnected-(U3-24_{slash}_TX6-Pad16)") (class "Default")
      (node (ref "U3") (pin "16") (pinfunction "24_/_TX6_16") (pintype "unspecified"))
    )
    (net (code "104") (name "unconnected-(U3-25_{slash}_RX6-Pad17)") (class "Default")
      (node (ref "U3") (pin "17") (pinfunction "25_/_RX6_17") (pintype "unspecified"))
    )
    (net (code "105") (name "unconnected-(U3-26-Pad18)") (class "Default")
      (node (ref "U3") (pin "18") (pinfunction "26_18") (pintype "unspecified"))
    )
    (net (code "106") (name "unconnected-(U3-27-Pad19)") (class "Default")
      (node (ref "U3") (pin "19") (pinfunction "27_19") (pintype "unspecified"))
    )
    (net (code "107") (name "unconnected-(U3-31-Pad23)") (class "Default")
      (node (ref "U3") (pin "23") (pinfunction "31_23") (pintype "unspecified"))
    )
    (net (code "108") (name "unconnected-(U3-GND-Pad39)") (class "Default")
      (node (ref "U3") (pin "39") (pinfunction "GND_39") (pintype "unspecified"))
    )
    (net (code "109") (name "unconnected-(U3-LED_{slash}_13-Pad38)") (class "Default")
      (node (ref "U3") (pin "38") (pinfunction "LED_/_13_38") (pintype "unspecified"))
    )
    (net (code "110") (name "unconnected-(U3-On_{slash}_Off-Pad49)") (class "Default")
      (node (ref "U3") (pin "49") (pinfunction "On_/_Off_49") (pintype "unspecified"))
    )
    (net (code "111") (name "unconnected-(U3-Prog-Pad50)") (class "Default")
      (node (ref "U3") (pin "50") (pinfunction "Prog_50") (pintype "unspecified"))
    )
    (net (code "112") (name "unconnected-(U3-RX3_{slash}_15-Pad36)") (class "Default")
      (node (ref "U3") (pin "36") (pinfunction "RX3_/_15_36") (pintype "unspecified"))
    )
    (net (code "113") (name "unconnected-(U3-RX5_{slash}_21-Pad30)") (class "Default")
      (node (ref "U3") (pin "30") (pinfunction "RX5_/_21_30") (pintype "unspecified"))
    )
    (net (code "114") (name "unconnected-(U3-RX8_{slash}_34-Pad47)") (class "Default")
      (node (ref "U3") (pin "47") (pinfunction "RX8_/_34_47") (pintype "unspecified"))
    )
    (net (code "115") (name "unconnected-(U3-TX8_{slash}_35-Pad46)") (class "Default")
      (node (ref "U3") (pin "46") (pinfunction "TX8_/_35_46") (pintype "unspecified"))
    )
    (net (code "116") (name "unconnected-(U3-VBat-Pad53)") (class "Default")
      (node (ref "U3") (pin "53") (pinfunction "VBat_53") (pintype "unspecified"))
    )
    (net (code "117") (name "unconnected-(U5-PG-Pad4)") (class "Default")
      (node (ref "U5") (pin "4") (pinfunction "PG_4") (pintype "unspecified"))
    )
    (net (code "118") (name "unconnected-(U5-SS-Pad5)") (class "Default")
      (node (ref "U5") (pin "5") (pinfunction "SS_5") (pintype "unspecified"))
    )
    (net (code "119") (name "unconnected-(U6-PG-Pad4)") (class "Default")
      (node (ref "U6") (pin "4") (pinfunction "PG_4") (pintype "unspecified"))
    )
    (net (code "120") (name "unconnected-(U6-SS-Pad5)") (class "Default")
      (node (ref "U6") (pin "5") (pinfunction "SS_5") (pintype "unspecified"))
    )
  )
)
